# RPiOperantPanelBreakout.net
KiCad netlist of a schematic drawn in EAGLE
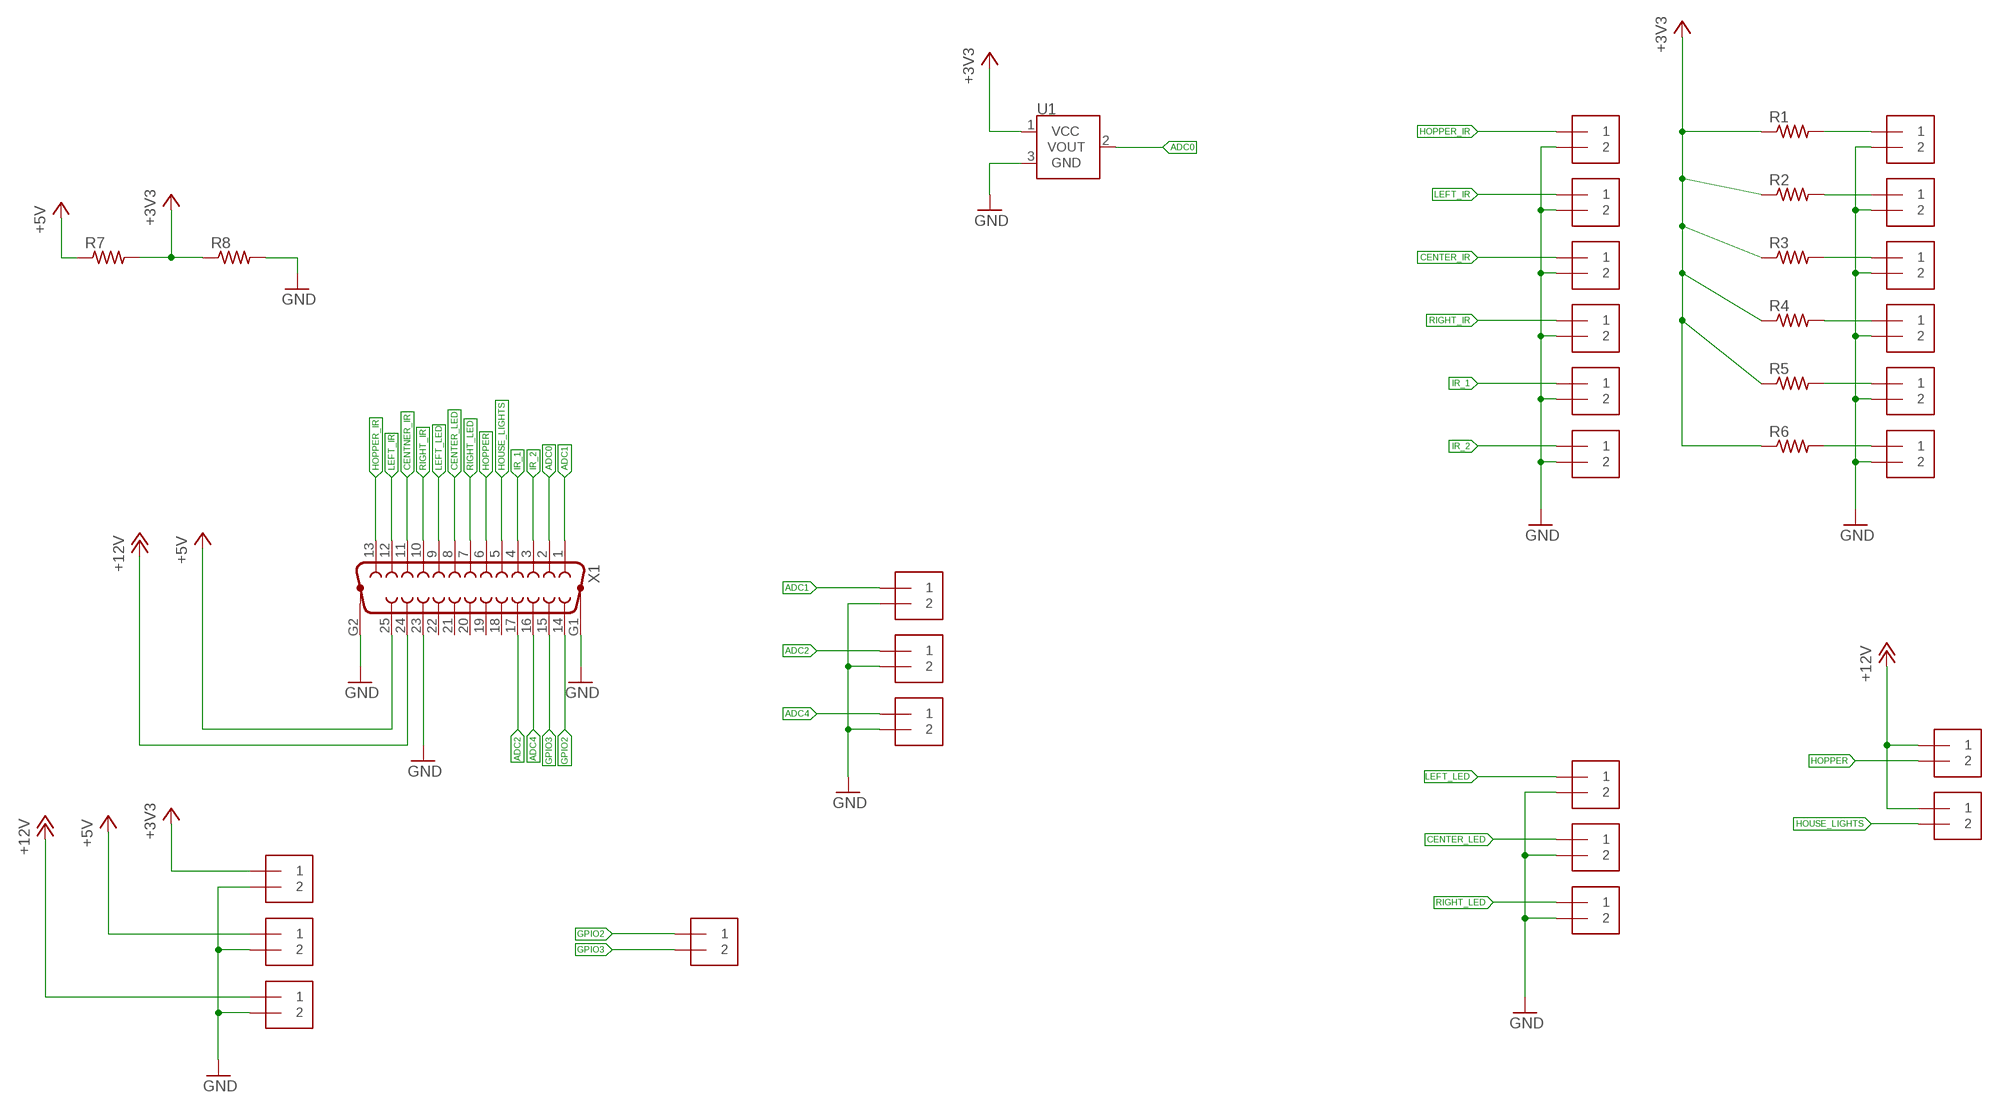
[diagram p0: schematic, sheet 1]

(export (version "E")
  (design (tool "Eeschema 10.0.6"))
  (components
    (comp (ref "J1")
      (value "1X2-3.5MM")
      (footprint "eagle-import:1X2-3.5MM")
      (libsource (lib "eagle-import") (part "1X2-3.5MM"))
    )
    (comp (ref "J2")
      (value "1X2-3.5MM")
      (footprint "eagle-import:1X2-3.5MM")
      (libsource (lib "eagle-import") (part "1X2-3.5MM"))
    )
    (comp (ref "J3")
      (value "1X2-3.5MM")
      (footprint "eagle-import:1X2-3.5MM")
      (libsource (lib "eagle-import") (part "1X2-3.5MM"))
    )
    (comp (ref "J4")
      (value "1X2-3.5MM")
      (footprint "eagle-import:1X2-3.5MM")
      (libsource (lib "eagle-import") (part "1X2-3.5MM"))
    )
    (comp (ref "J5")
      (value "1X2-3.5MM")
      (footprint "eagle-import:1X2-3.5MM")
      (libsource (lib "eagle-import") (part "1X2-3.5MM"))
    )
    (comp (ref "J6")
      (value "1X2-3.5MM")
      (footprint "eagle-import:1X2-3.5MM")
      (libsource (lib "eagle-import") (part "1X2-3.5MM"))
    )
    (comp (ref "J7")
      (value "1X2-3.5MM")
      (footprint "eagle-import:1X2-3.5MM")
      (libsource (lib "eagle-import") (part "1X2-3.5MM"))
    )
    (comp (ref "J8")
      (value "1X2-3.5MM")
      (footprint "eagle-import:1X2-3.5MM")
      (libsource (lib "eagle-import") (part "1X2-3.5MM"))
    )
    (comp (ref "J9")
      (value "1X2-3.5MM")
      (footprint "eagle-import:1X2-3.5MM")
      (libsource (lib "eagle-import") (part "1X2-3.5MM"))
    )
    (comp (ref "J10")
      (value "1X2-3.5MM")
      (footprint "eagle-import:1X2-3.5MM")
      (libsource (lib "eagle-import") (part "1X2-3.5MM"))
    )
    (comp (ref "J11")
      (value "1X2-3.5MM")
      (footprint "eagle-import:1X2-3.5MM")
      (libsource (lib "eagle-import") (part "1X2-3.5MM"))
    )
    (comp (ref "J12")
      (value "1X2-3.5MM")
      (footprint "eagle-import:1X2-3.5MM")
      (libsource (lib "eagle-import") (part "1X2-3.5MM"))
    )
    (comp (ref "J13")
      (value "1X2-3.5MM")
      (footprint "eagle-import:1X2-3.5MM")
      (libsource (lib "eagle-import") (part "1X2-3.5MM"))
    )
    (comp (ref "J14")
      (value "1X2-3.5MM")
      (footprint "eagle-import:1X2-3.5MM")
      (libsource (lib "eagle-import") (part "1X2-3.5MM"))
    )
    (comp (ref "J15")
      (value "1X2-3.5MM")
      (footprint "eagle-import:1X2-3.5MM")
      (libsource (lib "eagle-import") (part "1X2-3.5MM"))
    )
    (comp (ref "J16")
      (value "1X2-3.5MM")
      (footprint "eagle-import:1X2-3.5MM")
      (libsource (lib "eagle-import") (part "1X2-3.5MM"))
    )
    (comp (ref "J17")
      (value "1X2-3.5MM")
      (footprint "eagle-import:1X2-3.5MM")
      (libsource (lib "eagle-import") (part "1X2-3.5MM"))
    )
    (comp (ref "J18")
      (value "1X2-3.5MM")
      (footprint "eagle-import:1X2-3.5MM")
      (libsource (lib "eagle-import") (part "1X2-3.5MM"))
    )
    (comp (ref "J19")
      (value "1X2-3.5MM")
      (footprint "eagle-import:1X2-3.5MM")
      (libsource (lib "eagle-import") (part "1X2-3.5MM"))
    )
    (comp (ref "J20")
      (value "1X2-3.5MM")
      (footprint "eagle-import:1X2-3.5MM")
      (libsource (lib "eagle-import") (part "1X2-3.5MM"))
    )
    (comp (ref "J21")
      (value "1X2-3.5MM")
      (footprint "eagle-import:1X2-3.5MM")
      (libsource (lib "eagle-import") (part "1X2-3.5MM"))
    )
    (comp (ref "J22")
      (value "1X2-3.5MM")
      (footprint "eagle-import:1X2-3.5MM")
      (libsource (lib "eagle-import") (part "1X2-3.5MM"))
    )
    (comp (ref "J23")
      (value "1X2-3.5MM")
      (footprint "eagle-import:1X2-3.5MM")
      (libsource (lib "eagle-import") (part "1X2-3.5MM"))
    )
    (comp (ref "J24")
      (value "1X2-3.5MM")
      (footprint "eagle-import:1X2-3.5MM")
      (libsource (lib "eagle-import") (part "1X2-3.5MM"))
    )
    (comp (ref "R1")
      (value "R-US_0207/7")
      (footprint "eagle-import:0207_7")
      (libsource (lib "eagle-import") (part "R-US_0207/7"))
    )
    (comp (ref "R2")
      (value "R-US_0207/7")
      (footprint "eagle-import:0207_7")
      (libsource (lib "eagle-import") (part "R-US_0207/7"))
    )
    (comp (ref "R3")
      (value "R-US_0207/7")
      (footprint "eagle-import:0207_7")
      (libsource (lib "eagle-import") (part "R-US_0207/7"))
    )
    (comp (ref "R4")
      (value "R-US_0207/7")
      (footprint "eagle-import:0207_7")
      (libsource (lib "eagle-import") (part "R-US_0207/7"))
    )
    (comp (ref "R5")
      (value "R-US_0207/7")
      (footprint "eagle-import:0207_7")
      (libsource (lib "eagle-import") (part "R-US_0207/7"))
    )
    (comp (ref "R6")
      (value "R-US_0207/7")
      (footprint "eagle-import:0207_7")
      (libsource (lib "eagle-import") (part "R-US_0207/7"))
    )
    (comp (ref "R7")
      (value "R-US_0207/7")
      (footprint "eagle-import:0207_7")
      (libsource (lib "eagle-import") (part "R-US_0207/7"))
    )
    (comp (ref "R8")
      (value "R-US_0207/7")
      (footprint "eagle-import:0207_7")
      (libsource (lib "eagle-import") (part "R-US_0207/7"))
    )
    (comp (ref "U1")
      (value "TMP36GT9")
      (footprint "eagle-import:TO-92")
      (libsource (lib "eagle-import") (part "TMP36GT9"))
    )
    (comp (ref "X1")
      (value "F25HP")
      (footprint "eagle-import:F25HP")
      (libsource (lib "eagle-import") (part "F25HP"))
    )
  )
  (nets
    (net (code "1") (name "+3V3") (class "Default")
      (node (ref "J18") (pin "1") (pinfunction "1_1") (pintype "passive"))
      (node (ref "R1") (pin "1") (pinfunction "1_1") (pintype "passive"))
      (node (ref "R2") (pin "1") (pinfunction "1_1") (pintype "passive"))
      (node (ref "R3") (pin "1") (pinfunction "1_1") (pintype "passive"))
      (node (ref "R4") (pin "1") (pinfunction "1_1") (pintype "passive"))
      (node (ref "R5") (pin "1") (pinfunction "1_1") (pintype "passive"))
      (node (ref "R6") (pin "1") (pinfunction "1_1") (pintype "passive"))
      (node (ref "R7") (pin "2") (pinfunction "2_2") (pintype "passive"))
      (node (ref "R8") (pin "1") (pinfunction "1_1") (pintype "passive"))
      (node (ref "U1") (pin "1") (pinfunction "VCC_1") (pintype "bidirectional"))
    )
    (net (code "2") (name "+5V") (class "Default")
      (node (ref "J19") (pin "1") (pinfunction "1_1") (pintype "passive"))
      (node (ref "R7") (pin "1") (pinfunction "1_1") (pintype "passive"))
      (node (ref "X1") (pin "25") (pinfunction "25_25") (pintype "passive"))
    )
    (net (code "3") (name "+12V") (class "Default")
      (node (ref "J20") (pin "1") (pinfunction "1_1") (pintype "passive"))
      (node (ref "J7") (pin "1") (pinfunction "1_1") (pintype "passive"))
      (node (ref "J8") (pin "1") (pinfunction "1_1") (pintype "passive"))
      (node (ref "X1") (pin "24") (pinfunction "24_24") (pintype "passive"))
    )
    (net (code "4") (name "ADC0") (class "Default")
      (node (ref "U1") (pin "2") (pinfunction "VOUT_2") (pintype "bidirectional"))
      (node (ref "X1") (pin "2") (pinfunction "2_2") (pintype "passive"))
    )
    (net (code "5") (name "ADC1") (class "Default")
      (node (ref "J21") (pin "1") (pinfunction "1_1") (pintype "passive"))
      (node (ref "X1") (pin "1") (pinfunction "1_1") (pintype "passive"))
    )
    (net (code "6") (name "ADC2") (class "Default")
      (node (ref "J23") (pin "1") (pinfunction "1_1") (pintype "passive"))
      (node (ref "X1") (pin "17") (pinfunction "17_17") (pintype "passive"))
    )
    (net (code "7") (name "ADC4") (class "Default")
      (node (ref "J24") (pin "1") (pinfunction "1_1") (pintype "passive"))
      (node (ref "X1") (pin "16") (pinfunction "16_16") (pintype "passive"))
    )
    (net (code "8") (name "CENTER_IR") (class "Default")
      (node (ref "J3") (pin "1") (pinfunction "1_1") (pintype "passive"))
    )
    (net (code "9") (name "CENTER_LED") (class "Default")
      (node (ref "J10") (pin "1") (pinfunction "1_1") (pintype "passive"))
      (node (ref "X1") (pin "8") (pinfunction "8_8") (pintype "passive"))
    )
    (net (code "10") (name "CENTNER_IR") (class "Default")
      (node (ref "X1") (pin "11") (pinfunction "11_11") (pintype "passive"))
    )
    (net (code "11") (name "GND") (class "Default")
      (node (ref "J1") (pin "2") (pinfunction "2_2") (pintype "passive"))
      (node (ref "J10") (pin "2") (pinfunction "2_2") (pintype "passive"))
      (node (ref "J11") (pin "2") (pinfunction "2_2") (pintype "passive"))
      (node (ref "J12") (pin "2") (pinfunction "2_2") (pintype "passive"))
      (node (ref "J13") (pin "2") (pinfunction "2_2") (pintype "passive"))
      (node (ref "J14") (pin "2") (pinfunction "2_2") (pintype "passive"))
      (node (ref "J15") (pin "2") (pinfunction "2_2") (pintype "passive"))
      (node (ref "J16") (pin "2") (pinfunction "2_2") (pintype "passive"))
      (node (ref "J17") (pin "2") (pinfunction "2_2") (pintype "passive"))
      (node (ref "J18") (pin "2") (pinfunction "2_2") (pintype "passive"))
      (node (ref "J19") (pin "2") (pinfunction "2_2") (pintype "passive"))
      (node (ref "J2") (pin "2") (pinfunction "2_2") (pintype "passive"))
      (node (ref "J20") (pin "2") (pinfunction "2_2") (pintype "passive"))
      (node (ref "J21") (pin "2") (pinfunction "2_2") (pintype "passive"))
      (node (ref "J23") (pin "2") (pinfunction "2_2") (pintype "passive"))
      (node (ref "J24") (pin "2") (pinfunction "2_2") (pintype "passive"))
      (node (ref "J3") (pin "2") (pinfunction "2_2") (pintype "passive"))
      (node (ref "J4") (pin "2") (pinfunction "2_2") (pintype "passive"))
      (node (ref "J5") (pin "2") (pinfunction "2_2") (pintype "passive"))
      (node (ref "J6") (pin "2") (pinfunction "2_2") (pintype "passive"))
      (node (ref "J9") (pin "2") (pinfunction "2_2") (pintype "passive"))
      (node (ref "R8") (pin "2") (pinfunction "2_2") (pintype "passive"))
      (node (ref "U1") (pin "3") (pinfunction "GND_3") (pintype "bidirectional"))
      (node (ref "X1") (pin "23") (pinfunction "23_23") (pintype "passive"))
      (node (ref "X1") (pin "G1") (pinfunction "G1_G1") (pintype "passive"))
      (node (ref "X1") (pin "G2") (pinfunction "G2_G2") (pintype "passive"))
    )
    (net (code "12") (name "GPIO2") (class "Default")
      (node (ref "J22") (pin "1") (pinfunction "1_1") (pintype "passive"))
      (node (ref "X1") (pin "14") (pinfunction "14_14") (pintype "passive"))
    )
    (net (code "13") (name "GPIO3") (class "Default")
      (node (ref "J22") (pin "2") (pinfunction "2_2") (pintype "passive"))
      (node (ref "X1") (pin "15") (pinfunction "15_15") (pintype "passive"))
    )
    (net (code "14") (name "HOPPER") (class "Default")
      (node (ref "J7") (pin "2") (pinfunction "2_2") (pintype "passive"))
      (node (ref "X1") (pin "6") (pinfunction "6_6") (pintype "passive"))
    )
    (net (code "15") (name "HOPPER_IR") (class "Default")
      (node (ref "J1") (pin "1") (pinfunction "1_1") (pintype "passive"))
      (node (ref "X1") (pin "13") (pinfunction "13_13") (pintype "passive"))
    )
    (net (code "16") (name "HOUSE_LIGHTS") (class "Default")
      (node (ref "J8") (pin "2") (pinfunction "2_2") (pintype "passive"))
      (node (ref "X1") (pin "5") (pinfunction "5_5") (pintype "passive"))
    )
    (net (code "17") (name "IR_1") (class "Default")
      (node (ref "J5") (pin "1") (pinfunction "1_1") (pintype "passive"))
      (node (ref "X1") (pin "4") (pinfunction "4_4") (pintype "passive"))
    )
    (net (code "18") (name "IR_2") (class "Default")
      (node (ref "J6") (pin "1") (pinfunction "1_1") (pintype "passive"))
      (node (ref "X1") (pin "3") (pinfunction "3_3") (pintype "passive"))
    )
    (net (code "19") (name "LEFT_IR") (class "Default")
      (node (ref "J2") (pin "1") (pinfunction "1_1") (pintype "passive"))
      (node (ref "X1") (pin "12") (pinfunction "12_12") (pintype "passive"))
    )
    (net (code "20") (name "LEFT_LED") (class "Default")
      (node (ref "J9") (pin "1") (pinfunction "1_1") (pintype "passive"))
      (node (ref "X1") (pin "9") (pinfunction "9_9") (pintype "passive"))
    )
    (net (code "21") (name "Net-(J12-Pad1)") (class "Default")
      (node (ref "J12") (pin "1") (pinfunction "1_1") (pintype "passive"))
      (node (ref "R1") (pin "2") (pinfunction "2_2") (pintype "passive"))
    )
    (net (code "22") (name "Net-(J13-Pad1)") (class "Default")
      (node (ref "J13") (pin "1") (pinfunction "1_1") (pintype "passive"))
      (node (ref "R2") (pin "2") (pinfunction "2_2") (pintype "passive"))
    )
    (net (code "23") (name "Net-(J14-Pad1)") (class "Default")
      (node (ref "J14") (pin "1") (pinfunction "1_1") (pintype "passive"))
      (node (ref "R3") (pin "2") (pinfunction "2_2") (pintype "passive"))
    )
    (net (code "24") (name "Net-(J15-Pad1)") (class "Default")
      (node (ref "J15") (pin "1") (pinfunction "1_1") (pintype "passive"))
      (node (ref "R4") (pin "2") (pinfunction "2_2") (pintype "passive"))
    )
    (net (code "25") (name "Net-(J16-Pad1)") (class "Default")
      (node (ref "J16") (pin "1") (pinfunction "1_1") (pintype "passive"))
      (node (ref "R5") (pin "2") (pinfunction "2_2") (pintype "passive"))
    )
    (net (code "26") (name "Net-(J17-Pad1)") (class "Default")
      (node (ref "J17") (pin "1") (pinfunction "1_1") (pintype "passive"))
      (node (ref "R6") (pin "2") (pinfunction "2_2") (pintype "passive"))
    )
    (net (code "27") (name "RIGHT_IR") (class "Default")
      (node (ref "J4") (pin "1") (pinfunction "1_1") (pintype "passive"))
      (node (ref "X1") (pin "10") (pinfunction "10_10") (pintype "passive"))
    )
    (net (code "28") (name "RIGHT_LED") (class "Default")
      (node (ref "J11") (pin "1") (pinfunction "1_1") (pintype "passive"))
      (node (ref "X1") (pin "7") (pinfunction "7_7") (pintype "passive"))
    )
    (net (code "29") (name "unconnected-(X1-Pad18)") (class "Default")
      (node (ref "X1") (pin "18") (pinfunction "18_18") (pintype "passive"))
    )
    (net (code "30") (name "unconnected-(X1-Pad19)") (class "Default")
      (node (ref "X1") (pin "19") (pinfunction "19_19") (pintype "passive"))
    )
    (net (code "31") (name "unconnected-(X1-Pad20)") (class "Default")
      (node (ref "X1") (pin "20") (pinfunction "20_20") (pintype "passive"))
    )
    (net (code "32") (name "unconnected-(X1-Pad21)") (class "Default")
      (node (ref "X1") (pin "21") (pinfunction "21_21") (pintype "passive"))
    )
    (net (code "33") (name "unconnected-(X1-Pad22)") (class "Default")
      (node (ref "X1") (pin "22") (pinfunction "22_22") (pintype "passive"))
    )
  )
)
